# programmer_charger.net
KiCad netlist of a schematic drawn in Altium Designer
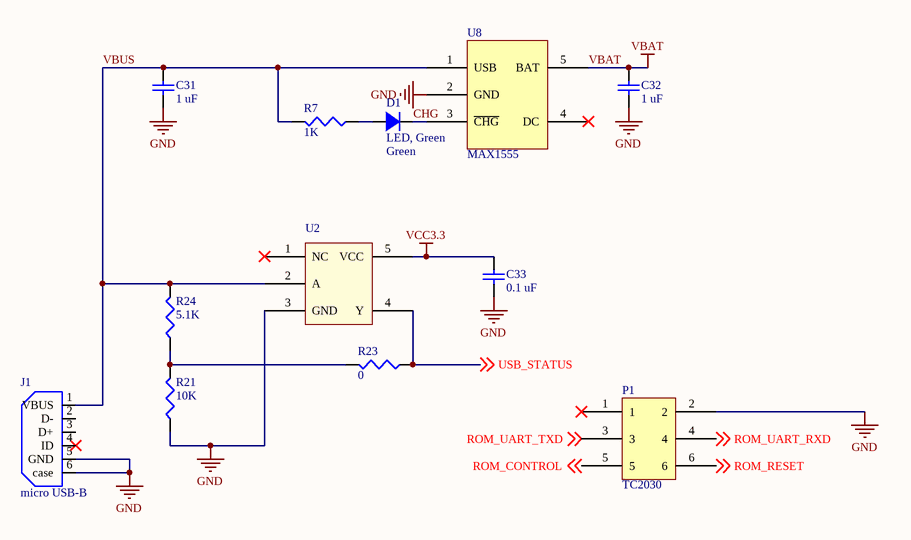
[diagram p0: programmer_charger.SchDoc]

(export (version "E")
  (design (tool "Eeschema 10.0.6"))
  (components
    (comp (ref "C31")
      (value "1 uF")
      (footprint "0402")
      (description "Ceramic capacitor, 1 uF, 0402 package")
      (fields (field (name "TOLERANCE") "10%") (field (name "Comment") "Ceramic capacitor"))
      (libsource (lib "rlc") (part "C_1u_0402_ceramic"))
    )
    (comp (ref "C32")
      (value "1 uF")
      (footprint "0402")
      (description "Ceramic capacitor, 1 uF, 0402 package")
      (fields (field (name "TOLERANCE") "10%") (field (name "Comment") "Ceramic capacitor"))
      (libsource (lib "rlc") (part "C_1u_0402_ceramic"))
    )
    (comp (ref "C33")
      (value "0.1 uF")
      (footprint "0402")
      (description "Ceramic capacitor, 0.1u, 0402 package")
      (fields (field (name "TOLERANCE") "10%") (field (name "Comment") "Ceramic capacitor"))
      (libsource (lib "rlc") (part "C_0.1u_0402_ceramic"))
    )
    (comp (ref "D1")
      (value "LED, Green")
      (footprint "0402 - DIODE")
      (description "LED, Green,  0402")
      (fields (field (name "COLOR") "Green"))
      (libsource (lib "rlc") (part "D_LED_GREEN_0402"))
    )
    (comp (ref "J1")
      (value "micro USB-B")
      (footprint "Micro USB-B")
      (description "CONN USB MICRO B RECPT SMT R/A")
      (libsource (lib "connectors") (part "Micro USB"))
    )
    (comp (ref "P1")
      (value "TC2030")
      (footprint "TC2030-IDC-NLFP")
      (description "TC2030-MCP-NL")
      (libsource (lib "connectors") (part "TC2030"))
    )
    (comp (ref "R7")
      (value "1K")
      (footprint "0402")
      (description "Chip resistor, 1K, 0402 package")
      (fields (field (name "TOLERANCE") "1%") (field (name "POWER") "1/16 W"))
      (libsource (lib "rlc") (part "R_1K_0402"))
    )
    (comp (ref "R21")
      (value "10K")
      (footprint "0402")
      (description "Chip resistor, 10K, 0402 package")
      (fields (field (name "TOLERANCE") "1%") (field (name "POWER") "1/16 W"))
      (libsource (lib "rlc") (part "R_10K_0402"))
    )
    (comp (ref "R23")
      (value "0")
      (footprint "0402")
      (description "Chip resistor, 0, 0402 package")
      (fields (field (name "Comment") "Chip resistor"))
      (libsource (lib "rlc") (part "R_0_0402"))
    )
    (comp (ref "R24")
      (value "5.1K")
      (footprint "0402")
      (description "Chip resistor, 5.1K,  0402 package")
      (fields (field (name "TOLERANCE") ".5%") (field (name "POWER") "1/16 W"))
      (libsource (lib "rlc") (part "R_5.1K_0402_1"))
    )
    (comp (ref "U2")
      (value "74LVC1G34GW")
      (footprint "SC-70-5 (DCK)")
      (description "Low power single buffer")
      (libsource (lib "logics") (part "74LVC1G34GW"))
    )
    (comp (ref "U8")
      (value "MAX1555")
      (footprint "SOT23-5")
      (description "3 Dual-Input USB/AC Adapter 1-Cell Li+  Battery Chargers")
      (libsource (lib "opo_general") (part "MAX1555"))
    )
  )
  (nets
    (net (code "1") (name "/CHG") (class "Default")
      (node (ref "D1") (pin "2") (pintype "passive"))
      (node (ref "U8") (pin "3") (pinfunction "~{CHG}_3") (pintype "passive"))
    )
    (net (code "2") (name "/VBUS") (class "Default")
      (node (ref "C31") (pin "1") (pintype "passive"))
      (node (ref "J1") (pin "1") (pinfunction "VBUS_1") (pintype "power_in"))
      (node (ref "R24") (pin "1") (pintype "passive"))
      (node (ref "R7") (pin "1") (pintype "passive"))
      (node (ref "U2") (pin "2") (pinfunction "A_2") (pintype "passive"))
      (node (ref "U8") (pin "1") (pinfunction "USB_1") (pintype "passive"))
    )
    (net (code "3") (name "GND") (class "Default")
      (node (ref "C31") (pin "2") (pintype "passive"))
      (node (ref "C32") (pin "2") (pintype "passive"))
      (node (ref "C33") (pin "2") (pintype "passive"))
      (node (ref "J1") (pin "5") (pinfunction "GND_5") (pintype "power_in"))
      (node (ref "J1") (pin "6") (pinfunction "case_6") (pintype "power_in"))
      (node (ref "P1") (pin "2") (pinfunction "2_2") (pintype "passive"))
      (node (ref "R21") (pin "2") (pintype "passive"))
      (node (ref "U2") (pin "3") (pinfunction "GND_3") (pintype "passive"))
      (node (ref "U8") (pin "2") (pinfunction "GND_2") (pintype "passive"))
    )
    (net (code "4") (name "Net-(D1-Pad1)") (class "Default")
      (node (ref "D1") (pin "1") (pintype "passive"))
      (node (ref "R7") (pin "2") (pintype "passive"))
    )
    (net (code "5") (name "Net-(R21-Pad1)") (class "Default")
      (node (ref "R21") (pin "1") (pintype "passive"))
      (node (ref "R23") (pin "1") (pintype "passive"))
      (node (ref "R24") (pin "2") (pintype "passive"))
    )
    (net (code "6") (name "ROM_CONTROL") (class "Default")
      (node (ref "P1") (pin "5") (pinfunction "5_5") (pintype "passive"))
    )
    (net (code "7") (name "ROM_RESET") (class "Default")
      (node (ref "P1") (pin "6") (pinfunction "6_6") (pintype "passive"))
    )
    (net (code "8") (name "ROM_UART_RXD") (class "Default")
      (node (ref "P1") (pin "4") (pinfunction "4_4") (pintype "passive"))
    )
    (net (code "9") (name "ROM_UART_TXD") (class "Default")
      (node (ref "P1") (pin "3") (pinfunction "3_3") (pintype "passive"))
    )
    (net (code "10") (name "USB_STATUS") (class "Default")
      (node (ref "R23") (pin "2") (pintype "passive"))
      (node (ref "U2") (pin "4") (pinfunction "Y_4") (pintype "passive"))
    )
    (net (code "11") (name "VBAT") (class "Default")
      (node (ref "C32") (pin "1") (pintype "passive"))
      (node (ref "U8") (pin "5") (pinfunction "BAT_5") (pintype "passive"))
    )
    (net (code "12") (name "VCC3.3") (class "Default")
      (node (ref "C33") (pin "1") (pintype "passive"))
      (node (ref "U2") (pin "5") (pinfunction "VCC_5") (pintype "passive"))
    )
    (net (code "13") (name "unconnected-(J1-D+-Pad3)") (class "Default")
      (node (ref "J1") (pin "3") (pinfunction "D+_3") (pintype "power_in"))
    )
    (net (code "14") (name "unconnected-(J1-D--Pad2)") (class "Default")
      (node (ref "J1") (pin "2") (pinfunction "D-_2") (pintype "power_in"))
    )
    (net (code "15") (name "unconnected-(J1-ID-Pad4)") (class "Default")
      (node (ref "J1") (pin "4") (pinfunction "ID_4") (pintype "power_in+no_connect"))
    )
    (net (code "16") (name "unconnected-(P1-Pad1)") (class "Default")
      (node (ref "P1") (pin "1") (pinfunction "1_1") (pintype "passive+no_connect"))
    )
    (net (code "17") (name "unconnected-(U2-NC-Pad1)") (class "Default")
      (node (ref "U2") (pin "1") (pinfunction "NC_1") (pintype "passive+no_connect"))
    )
    (net (code "18") (name "unconnected-(U8-DC-Pad4)") (class "Default")
      (node (ref "U8") (pin "4") (pinfunction "DC_4") (pintype "passive+no_connect"))
    )
  )
)
